# PERfECT-PRO.net
KiCad netlist of a schematic drawn in Altium Designer
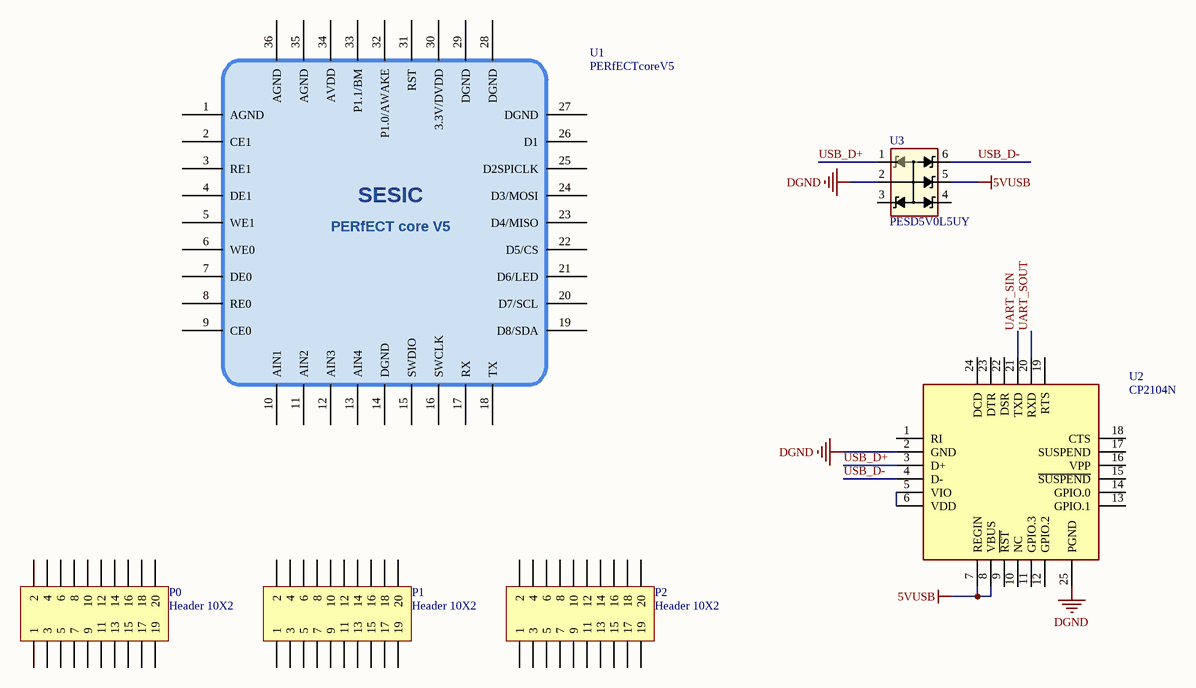
[diagram p0: PERfECT-PRO.SchDoc]

(export (version "E")
  (design (tool "Eeschema 10.0.6"))
  (components
    (comp (ref "P0")
      (value "Header 10X2")
      (footprint "HDR2X10")
      (description "Header, 10-Pin, Dual row")
      (fields (field (name "PUBLISHER") "Altium Limited"))
      (libsource (lib "Miscellaneous Connectors") (part "Header 10X2"))
    )
    (comp (ref "P1")
      (value "Header 10X2")
      (footprint "HDR2X10")
      (description "Header, 10-Pin, Dual row")
      (fields (field (name "PUBLISHER") "Altium Limited"))
      (libsource (lib "Miscellaneous Connectors") (part "Header 10X2"))
    )
    (comp (ref "P2")
      (value "Header 10X2")
      (footprint "HDR2X10")
      (description "Header, 10-Pin, Dual row")
      (fields (field (name "PUBLISHER") "Altium Limited"))
      (libsource (lib "Miscellaneous Connectors") (part "Header 10X2"))
    )
    (comp (ref "U1")
      (value "PERfECTcoreV5")
      (footprint "PERfECTcore36")
      (description "This is the 5th version of PERfEC core.https://github.com/WISE-PERfECT/PERfECT")
      (libsource (lib "PERfECT") (part "PERfECTcoreV5"))
    )
    (comp (ref "U2")
      (value "CP2104N")
      (footprint "24-QFN")
      (description "IC BRIDGE USB TO UART 24QFN")
      (fields (field (name "MANUFACTURER") "Silicon Labs") (field (name "PARTNUMBER") "C47742"))
      (libsource (lib "W24E32v2") (part "CP2104N"))
    )
    (comp (ref "U3")
      (value "PESD5V0L5UY")
      (footprint "SOT65P210X110-6N")
      (description "TVS SOT-363 RoHS")
      (fields (field (name "MANUFACTURER") "Yenji") (field (name "PARTNUMBER") "PESD5V0L5UY"))
      (libsource (lib "W24E32v2") (part "PESD5V0L5UY"))
    )
  )
  (nets
    (net (code "1") (name "/UART_SIN") (class "Default")
      (node (ref "U2") (pin "21") (pinfunction "TXD_21") (pintype "passive"))
    )
    (net (code "2") (name "/UART_SOUT") (class "Default")
      (node (ref "U2") (pin "20") (pinfunction "RXD_20") (pintype "passive"))
    )
    (net (code "3") (name "/USB_D+") (class "Default")
      (node (ref "U2") (pin "3") (pinfunction "D+_3") (pintype "passive"))
      (node (ref "U3") (pin "1") (pinfunction "1_1") (pintype "passive"))
    )
    (net (code "4") (name "/USB_D-") (class "Default")
      (node (ref "U2") (pin "4") (pinfunction "D-_4") (pintype "passive"))
      (node (ref "U3") (pin "6") (pinfunction "6_6") (pintype "passive"))
    )
    (net (code "5") (name "5VUSB") (class "Default")
      (node (ref "U2") (pin "7") (pinfunction "REGIN_7") (pintype "power_in"))
      (node (ref "U2") (pin "8") (pinfunction "VBUS_8") (pintype "power_in"))
      (node (ref "U3") (pin "5") (pinfunction "5_5") (pintype "passive"))
    )
    (net (code "6") (name "DGND") (class "Default")
      (node (ref "U2") (pin "2") (pinfunction "GND_2") (pintype "power_in"))
      (node (ref "U2") (pin "25") (pinfunction "PGND_25") (pintype "passive"))
      (node (ref "U3") (pin "2") (pinfunction "2_2") (pintype "passive"))
    )
    (net (code "7") (name "Net-(U2-VDD)") (class "Default")
      (node (ref "U2") (pin "5") (pinfunction "VIO_5") (pintype "power_in"))
      (node (ref "U2") (pin "6") (pinfunction "VDD_6") (pintype "power_in"))
    )
    (net (code "8") (name "unconnected-(P0-Pad1)") (class "Default")
      (node (ref "P0") (pin "1") (pinfunction "1_1") (pintype "passive"))
    )
    (net (code "9") (name "unconnected-(P0-Pad2)") (class "Default")
      (node (ref "P0") (pin "2") (pinfunction "2_2") (pintype "passive"))
    )
    (net (code "10") (name "unconnected-(P0-Pad3)") (class "Default")
      (node (ref "P0") (pin "3") (pinfunction "3_3") (pintype "passive"))
    )
    (net (code "11") (name "unconnected-(P0-Pad4)") (class "Default")
      (node (ref "P0") (pin "4") (pinfunction "4_4") (pintype "passive"))
    )
    (net (code "12") (name "unconnected-(P0-Pad5)") (class "Default")
      (node (ref "P0") (pin "5") (pinfunction "5_5") (pintype "passive"))
    )
    (net (code "13") (name "unconnected-(P0-Pad6)") (class "Default")
      (node (ref "P0") (pin "6") (pinfunction "6_6") (pintype "passive"))
    )
    (net (code "14") (name "unconnected-(P0-Pad7)") (class "Default")
      (node (ref "P0") (pin "7") (pinfunction "7_7") (pintype "passive"))
    )
    (net (code "15") (name "unconnected-(P0-Pad8)") (class "Default")
      (node (ref "P0") (pin "8") (pinfunction "8_8") (pintype "passive"))
    )
    (net (code "16") (name "unconnected-(P0-Pad9)") (class "Default")
      (node (ref "P0") (pin "9") (pinfunction "9_9") (pintype "passive"))
    )
    (net (code "17") (name "unconnected-(P0-Pad10)") (class "Default")
      (node (ref "P0") (pin "10") (pinfunction "10_10") (pintype "passive"))
    )
    (net (code "18") (name "unconnected-(P0-Pad11)") (class "Default")
      (node (ref "P0") (pin "11") (pinfunction "11_11") (pintype "passive"))
    )
    (net (code "19") (name "unconnected-(P0-Pad12)") (class "Default")
      (node (ref "P0") (pin "12") (pinfunction "12_12") (pintype "passive"))
    )
    (net (code "20") (name "unconnected-(P0-Pad13)") (class "Default")
      (node (ref "P0") (pin "13") (pinfunction "13_13") (pintype "passive"))
    )
    (net (code "21") (name "unconnected-(P0-Pad14)") (class "Default")
      (node (ref "P0") (pin "14") (pinfunction "14_14") (pintype "passive"))
    )
    (net (code "22") (name "unconnected-(P0-Pad15)") (class "Default")
      (node (ref "P0") (pin "15") (pinfunction "15_15") (pintype "passive"))
    )
    (net (code "23") (name "unconnected-(P0-Pad16)") (class "Default")
      (node (ref "P0") (pin "16") (pinfunction "16_16") (pintype "passive"))
    )
    (net (code "24") (name "unconnected-(P0-Pad17)") (class "Default")
      (node (ref "P0") (pin "17") (pinfunction "17_17") (pintype "passive"))
    )
    (net (code "25") (name "unconnected-(P0-Pad18)") (class "Default")
      (node (ref "P0") (pin "18") (pinfunction "18_18") (pintype "passive"))
    )
    (net (code "26") (name "unconnected-(P0-Pad19)") (class "Default")
      (node (ref "P0") (pin "19") (pinfunction "19_19") (pintype "passive"))
    )
    (net (code "27") (name "unconnected-(P0-Pad20)") (class "Default")
      (node (ref "P0") (pin "20") (pinfunction "20_20") (pintype "passive"))
    )
    (net (code "28") (name "unconnected-(P1-Pad1)") (class "Default")
      (node (ref "P1") (pin "1") (pinfunction "1_1") (pintype "passive"))
    )
    (net (code "29") (name "unconnected-(P1-Pad2)") (class "Default")
      (node (ref "P1") (pin "2") (pinfunction "2_2") (pintype "passive"))
    )
    (net (code "30") (name "unconnected-(P1-Pad3)") (class "Default")
      (node (ref "P1") (pin "3") (pinfunction "3_3") (pintype "passive"))
    )
    (net (code "31") (name "unconnected-(P1-Pad4)") (class "Default")
      (node (ref "P1") (pin "4") (pinfunction "4_4") (pintype "passive"))
    )
    (net (code "32") (name "unconnected-(P1-Pad5)") (class "Default")
      (node (ref "P1") (pin "5") (pinfunction "5_5") (pintype "passive"))
    )
    (net (code "33") (name "unconnected-(P1-Pad6)") (class "Default")
      (node (ref "P1") (pin "6") (pinfunction "6_6") (pintype "passive"))
    )
    (net (code "34") (name "unconnected-(P1-Pad7)") (class "Default")
      (node (ref "P1") (pin "7") (pinfunction "7_7") (pintype "passive"))
    )
    (net (code "35") (name "unconnected-(P1-Pad8)") (class "Default")
      (node (ref "P1") (pin "8") (pinfunction "8_8") (pintype "passive"))
    )
    (net (code "36") (name "unconnected-(P1-Pad9)") (class "Default")
      (node (ref "P1") (pin "9") (pinfunction "9_9") (pintype "passive"))
    )
    (net (code "37") (name "unconnected-(P1-Pad10)") (class "Default")
      (node (ref "P1") (pin "10") (pinfunction "10_10") (pintype "passive"))
    )
    (net (code "38") (name "unconnected-(P1-Pad11)") (class "Default")
      (node (ref "P1") (pin "11") (pinfunction "11_11") (pintype "passive"))
    )
    (net (code "39") (name "unconnected-(P1-Pad12)") (class "Default")
      (node (ref "P1") (pin "12") (pinfunction "12_12") (pintype "passive"))
    )
    (net (code "40") (name "unconnected-(P1-Pad13)") (class "Default")
      (node (ref "P1") (pin "13") (pinfunction "13_13") (pintype "passive"))
    )
    (net (code "41") (name "unconnected-(P1-Pad14)") (class "Default")
      (node (ref "P1") (pin "14") (pinfunction "14_14") (pintype "passive"))
    )
    (net (code "42") (name "unconnected-(P1-Pad15)") (class "Default")
      (node (ref "P1") (pin "15") (pinfunction "15_15") (pintype "passive"))
    )
    (net (code "43") (name "unconnected-(P1-Pad16)") (class "Default")
      (node (ref "P1") (pin "16") (pinfunction "16_16") (pintype "passive"))
    )
    (net (code "44") (name "unconnected-(P1-Pad17)") (class "Default")
      (node (ref "P1") (pin "17") (pinfunction "17_17") (pintype "passive"))
    )
    (net (code "45") (name "unconnected-(P1-Pad18)") (class "Default")
      (node (ref "P1") (pin "18") (pinfunction "18_18") (pintype "passive"))
    )
    (net (code "46") (name "unconnected-(P1-Pad19)") (class "Default")
      (node (ref "P1") (pin "19") (pinfunction "19_19") (pintype "passive"))
    )
    (net (code "47") (name "unconnected-(P1-Pad20)") (class "Default")
      (node (ref "P1") (pin "20") (pinfunction "20_20") (pintype "passive"))
    )
    (net (code "48") (name "unconnected-(P2-Pad1)") (class "Default")
      (node (ref "P2") (pin "1") (pinfunction "1_1") (pintype "passive"))
    )
    (net (code "49") (name "unconnected-(P2-Pad2)") (class "Default")
      (node (ref "P2") (pin "2") (pinfunction "2_2") (pintype "passive"))
    )
    (net (code "50") (name "unconnected-(P2-Pad3)") (class "Default")
      (node (ref "P2") (pin "3") (pinfunction "3_3") (pintype "passive"))
    )
    (net (code "51") (name "unconnected-(P2-Pad4)") (class "Default")
      (node (ref "P2") (pin "4") (pinfunction "4_4") (pintype "passive"))
    )
    (net (code "52") (name "unconnected-(P2-Pad5)") (class "Default")
      (node (ref "P2") (pin "5") (pinfunction "5_5") (pintype "passive"))
    )
    (net (code "53") (name "unconnected-(P2-Pad6)") (class "Default")
      (node (ref "P2") (pin "6") (pinfunction "6_6") (pintype "passive"))
    )
    (net (code "54") (name "unconnected-(P2-Pad7)") (class "Default")
      (node (ref "P2") (pin "7") (pinfunction "7_7") (pintype "passive"))
    )
    (net (code "55") (name "unconnected-(P2-Pad8)") (class "Default")
      (node (ref "P2") (pin "8") (pinfunction "8_8") (pintype "passive"))
    )
    (net (code "56") (name "unconnected-(P2-Pad9)") (class "Default")
      (node (ref "P2") (pin "9") (pinfunction "9_9") (pintype "passive"))
    )
    (net (code "57") (name "unconnected-(P2-Pad10)") (class "Default")
      (node (ref "P2") (pin "10") (pinfunction "10_10") (pintype "passive"))
    )
    (net (code "58") (name "unconnected-(P2-Pad11)") (class "Default")
      (node (ref "P2") (pin "11") (pinfunction "11_11") (pintype "passive"))
    )
    (net (code "59") (name "unconnected-(P2-Pad12)") (class "Default")
      (node (ref "P2") (pin "12") (pinfunction "12_12") (pintype "passive"))
    )
    (net (code "60") (name "unconnected-(P2-Pad13)") (class "Default")
      (node (ref "P2") (pin "13") (pinfunction "13_13") (pintype "passive"))
    )
    (net (code "61") (name "unconnected-(P2-Pad14)") (class "Default")
      (node (ref "P2") (pin "14") (pinfunction "14_14") (pintype "passive"))
    )
    (net (code "62") (name "unconnected-(P2-Pad15)") (class "Default")
      (node (ref "P2") (pin "15") (pinfunction "15_15") (pintype "passive"))
    )
    (net (code "63") (name "unconnected-(P2-Pad16)") (class "Default")
      (node (ref "P2") (pin "16") (pinfunction "16_16") (pintype "passive"))
    )
    (net (code "64") (name "unconnected-(P2-Pad17)") (class "Default")
      (node (ref "P2") (pin "17") (pinfunction "17_17") (pintype "passive"))
    )
    (net (code "65") (name "unconnected-(P2-Pad18)") (class "Default")
      (node (ref "P2") (pin "18") (pinfunction "18_18") (pintype "passive"))
    )
    (net (code "66") (name "unconnected-(P2-Pad19)") (class "Default")
      (node (ref "P2") (pin "19") (pinfunction "19_19") (pintype "passive"))
    )
    (net (code "67") (name "unconnected-(P2-Pad20)") (class "Default")
      (node (ref "P2") (pin "20") (pinfunction "20_20") (pintype "passive"))
    )
    (net (code "68") (name "unconnected-(U1-3.3V{slash}DVDD-Pad30)") (class "Default")
      (node (ref "U1") (pin "30") (pinfunction "3.3V/DVDD_30") (pintype "passive"))
    )
    (net (code "69") (name "unconnected-(U1-AGND-Pad1)") (class "Default")
      (node (ref "U1") (pin "1") (pinfunction "AGND_1") (pintype "passive"))
    )
    (net (code "70") (name "unconnected-(U1-AGND-Pad35)") (class "Default")
      (node (ref "U1") (pin "35") (pinfunction "AGND_35") (pintype "passive"))
    )
    (net (code "71") (name "unconnected-(U1-AGND-Pad36)") (class "Default")
      (node (ref "U1") (pin "36") (pinfunction "AGND_36") (pintype "passive"))
    )
    (net (code "72") (name "unconnected-(U1-AIN1-Pad10)") (class "Default")
      (node (ref "U1") (pin "10") (pinfunction "AIN1_10") (pintype "passive"))
    )
    (net (code "73") (name "unconnected-(U1-AIN2-Pad11)") (class "Default")
      (node (ref "U1") (pin "11") (pinfunction "AIN2_11") (pintype "passive"))
    )
    (net (code "74") (name "unconnected-(U1-AIN3-Pad12)") (class "Default")
      (node (ref "U1") (pin "12") (pinfunction "AIN3_12") (pintype "passive"))
    )
    (net (code "75") (name "unconnected-(U1-AIN4-Pad13)") (class "Default")
      (node (ref "U1") (pin "13") (pinfunction "AIN4_13") (pintype "passive"))
    )
    (net (code "76") (name "unconnected-(U1-AVDD-Pad34)") (class "Default")
      (node (ref "U1") (pin "34") (pinfunction "AVDD_34") (pintype "passive"))
    )
    (net (code "77") (name "unconnected-(U1-CE0-Pad9)") (class "Default")
      (node (ref "U1") (pin "9") (pinfunction "CE0_9") (pintype "passive"))
    )
    (net (code "78") (name "unconnected-(U1-CE1-Pad2)") (class "Default")
      (node (ref "U1") (pin "2") (pinfunction "CE1_2") (pintype "passive"))
    )
    (net (code "79") (name "unconnected-(U1-D1-Pad26)") (class "Default")
      (node (ref "U1") (pin "26") (pinfunction "D1_26") (pintype "passive"))
    )
    (net (code "80") (name "unconnected-(U1-D2SPICLK-Pad25)") (class "Default")
      (node (ref "U1") (pin "25") (pinfunction "D2SPICLK_25") (pintype "passive"))
    )
    (net (code "81") (name "unconnected-(U1-D3{slash}MOSI-Pad24)") (class "Default")
      (node (ref "U1") (pin "24") (pinfunction "D3/MOSI_24") (pintype "passive"))
    )
    (net (code "82") (name "unconnected-(U1-D4{slash}MISO-Pad23)") (class "Default")
      (node (ref "U1") (pin "23") (pinfunction "D4/MISO_23") (pintype "passive"))
    )
    (net (code "83") (name "unconnected-(U1-D5{slash}CS-Pad22)") (class "Default")
      (node (ref "U1") (pin "22") (pinfunction "D5/CS_22") (pintype "passive"))
    )
    (net (code "84") (name "unconnected-(U1-D6{slash}LED-Pad21)") (class "Default")
      (node (ref "U1") (pin "21") (pinfunction "D6/LED_21") (pintype "passive"))
    )
    (net (code "85") (name "unconnected-(U1-D7{slash}SCL-Pad20)") (class "Default")
      (node (ref "U1") (pin "20") (pinfunction "D7/SCL_20") (pintype "passive"))
    )
    (net (code "86") (name "unconnected-(U1-D8{slash}SDA-Pad19)") (class "Default")
      (node (ref "U1") (pin "19") (pinfunction "D8/SDA_19") (pintype "passive"))
    )
    (net (code "87") (name "unconnected-(U1-DE0-Pad7)") (class "Default")
      (node (ref "U1") (pin "7") (pinfunction "DE0_7") (pintype "passive"))
    )
    (net (code "88") (name "unconnected-(U1-DE1-Pad4)") (class "Default")
      (node (ref "U1") (pin "4") (pinfunction "DE1_4") (pintype "passive"))
    )
    (net (code "89") (name "unconnected-(U1-DGND-Pad14)") (class "Default")
      (node (ref "U1") (pin "14") (pinfunction "DGND_14") (pintype "passive"))
    )
    (net (code "90") (name "unconnected-(U1-DGND-Pad27)") (class "Default")
      (node (ref "U1") (pin "27") (pinfunction "DGND_27") (pintype "passive"))
    )
    (net (code "91") (name "unconnected-(U1-DGND-Pad28)") (class "Default")
      (node (ref "U1") (pin "28") (pinfunction "DGND_28") (pintype "power_in"))
    )
    (net (code "92") (name "unconnected-(U1-DGND-Pad29)") (class "Default")
      (node (ref "U1") (pin "29") (pinfunction "DGND_29") (pintype "passive"))
    )
    (net (code "93") (name "unconnected-(U1-P1.0{slash}AWAKE-Pad32)") (class "Default")
      (node (ref "U1") (pin "32") (pinfunction "P1.0/AWAKE_32") (pintype "passive"))
    )
    (net (code "94") (name "unconnected-(U1-P1.1{slash}BM-Pad33)") (class "Default")
      (node (ref "U1") (pin "33") (pinfunction "P1.1/BM_33") (pintype "passive"))
    )
    (net (code "95") (name "unconnected-(U1-RE0-Pad8)") (class "Default")
      (node (ref "U1") (pin "8") (pinfunction "RE0_8") (pintype "passive"))
    )
    (net (code "96") (name "unconnected-(U1-RE1-Pad3)") (class "Default")
      (node (ref "U1") (pin "3") (pinfunction "RE1_3") (pintype "passive"))
    )
    (net (code "97") (name "unconnected-(U1-RST-Pad31)") (class "Default")
      (node (ref "U1") (pin "31") (pinfunction "RST_31") (pintype "passive"))
    )
    (net (code "98") (name "unconnected-(U1-RX-Pad17)") (class "Default")
      (node (ref "U1") (pin "17") (pinfunction "RX_17") (pintype "passive"))
    )
    (net (code "99") (name "unconnected-(U1-SWCLK-Pad16)") (class "Default")
      (node (ref "U1") (pin "16") (pinfunction "SWCLK_16") (pintype "passive"))
    )
    (net (code "100") (name "unconnected-(U1-SWDIO-Pad15)") (class "Default")
      (node (ref "U1") (pin "15") (pinfunction "SWDIO_15") (pintype "passive"))
    )
    (net (code "101") (name "unconnected-(U1-TX-Pad18)") (class "Default")
      (node (ref "U1") (pin "18") (pinfunction "TX_18") (pintype "passive"))
    )
    (net (code "102") (name "unconnected-(U1-WE0-Pad6)") (class "Default")
      (node (ref "U1") (pin "6") (pinfunction "WE0_6") (pintype "passive"))
    )
    (net (code "103") (name "unconnected-(U1-WE1-Pad5)") (class "Default")
      (node (ref "U1") (pin "5") (pinfunction "WE1_5") (pintype "passive"))
    )
    (net (code "104") (name "unconnected-(U2-CTS-Pad18)") (class "Default")
      (node (ref "U2") (pin "18") (pinfunction "CTS_18") (pintype "passive"))
    )
    (net (code "105") (name "unconnected-(U2-DCD-Pad24)") (class "Default")
      (node (ref "U2") (pin "24") (pinfunction "DCD_24") (pintype "passive"))
    )
    (net (code "106") (name "unconnected-(U2-DSR-Pad22)") (class "Default")
      (node (ref "U2") (pin "22") (pinfunction "DSR_22") (pintype "passive"))
    )
    (net (code "107") (name "unconnected-(U2-DTR-Pad23)") (class "Default")
      (node (ref "U2") (pin "23") (pinfunction "DTR_23") (pintype "passive"))
    )
    (net (code "108") (name "unconnected-(U2-GPIO.0-Pad14)") (class "Default")
      (node (ref "U2") (pin "14") (pinfunction "GPIO.0_14") (pintype "passive"))
    )
    (net (code "109") (name "unconnected-(U2-GPIO.1-Pad13)") (class "Default")
      (node (ref "U2") (pin "13") (pinfunction "GPIO.1_13") (pintype "passive"))
    )
    (net (code "110") (name "unconnected-(U2-GPIO.2-Pad12)") (class "Default")
      (node (ref "U2") (pin "12") (pinfunction "GPIO.2_12") (pintype "passive"))
    )
    (net (code "111") (name "unconnected-(U2-GPIO.3-Pad11)") (class "Default")
      (node (ref "U2") (pin "11") (pinfunction "GPIO.3_11") (pintype "passive"))
    )
    (net (code "112") (name "unconnected-(U2-NC-Pad10)") (class "Default")
      (node (ref "U2") (pin "10") (pinfunction "NC_10") (pintype "passive"))
    )
    (net (code "113") (name "unconnected-(U2-RI-Pad1)") (class "Default")
      (node (ref "U2") (pin "1") (pinfunction "RI_1") (pintype "passive"))
    )
    (net (code "114") (name "unconnected-(U2-RTS-Pad19)") (class "Default")
      (node (ref "U2") (pin "19") (pinfunction "RTS_19") (pintype "passive"))
    )
    (net (code "115") (name "unconnected-(U2-SUSPEND-Pad17)") (class "Default")
      (node (ref "U2") (pin "17") (pinfunction "SUSPEND_17") (pintype "passive"))
    )
    (net (code "116") (name "unconnected-(U2-VPP-Pad16)") (class "Default")
      (node (ref "U2") (pin "16") (pinfunction "VPP_16") (pintype "passive"))
    )
    (net (code "117") (name "unconnected-(U2-~{RST}-Pad9)") (class "Default")
      (node (ref "U2") (pin "9") (pinfunction "~{RST}_9") (pintype "passive"))
    )
    (net (code "118") (name "unconnected-(U2-~{SUSPEND}-Pad15)") (class "Default")
      (node (ref "U2") (pin "15") (pinfunction "~{SUSPEND}_15") (pintype "passive"))
    )
    (net (code "119") (name "unconnected-(U3-Pad3)") (class "Default")
      (node (ref "U3") (pin "3") (pinfunction "3_3") (pintype "passive"))
    )
    (net (code "120") (name "unconnected-(U3-Pad4)") (class "Default")
      (node (ref "U3") (pin "4") (pinfunction "4_4") (pintype "passive"))
    )
  )
)
